# node-circuit-board-v0.net
KiCad netlist of a schematic drawn in EAGLE
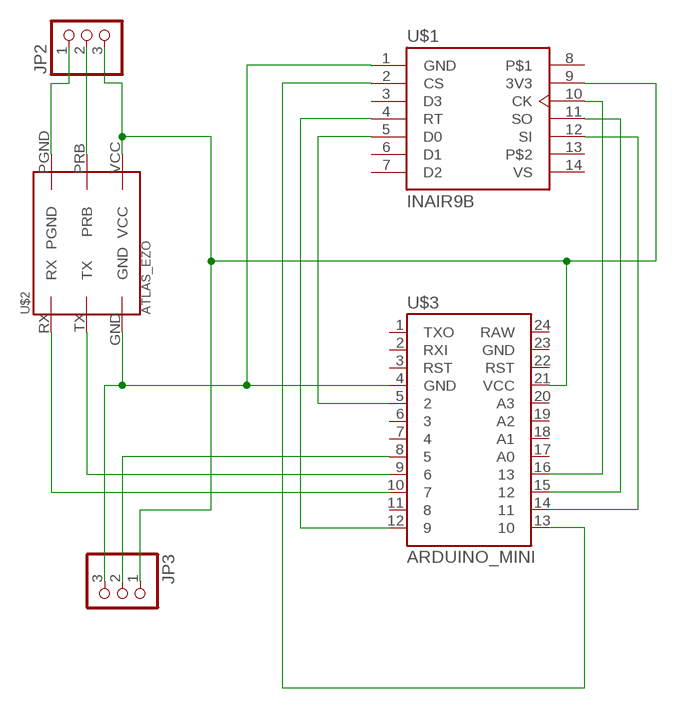
[diagram p0: schematic, sheet 1]

(export (version "E")
  (design (tool "Eeschema 10.0.6"))
  (components
    (comp (ref "JP2")
      (value "PINHD-1X3CB")
      (footprint "eagle-import:1X03-CLEANBIG")
      (libsource (lib "eagle-import") (part "PINHD-1X3CB"))
    )
    (comp (ref "JP3")
      (value "PINHD-1X3CB")
      (footprint "eagle-import:1X03-CLEANBIG")
      (libsource (lib "eagle-import") (part "PINHD-1X3CB"))
    )
    (comp (ref "U$1")
      (value "INAIR9B")
      (footprint "eagle-import:INAIR")
      (libsource (lib "eagle-import") (part "INAIR9B"))
    )
    (comp (ref "U$2")
      (value "ATLAS_EZO")
      (footprint "eagle-import:ATLAS_EZO")
      (libsource (lib "eagle-import") (part "ATLAS_EZO"))
    )
    (comp (ref "U$3")
      (value "ARDUINO_MINI")
      (footprint "eagle-import:ARDUINO_MINI")
      (libsource (lib "eagle-import") (part "ARDUINO_MINI"))
    )
  )
  (nets
    (net (code "1") (name "Net-(JP2-Pad1)") (class "Default")
      (node (ref "JP2") (pin "1") (pinfunction "1_1") (pintype "passive"))
      (node (ref "U$2") (pin "PGND") (pinfunction "PGND_PGND") (pintype "bidirectional"))
    )
    (net (code "2") (name "Net-(JP2-Pad2)") (class "Default")
      (node (ref "JP2") (pin "2") (pinfunction "2_2") (pintype "passive"))
      (node (ref "U$2") (pin "PRB") (pinfunction "PRB_PRB") (pintype "bidirectional"))
    )
    (net (code "3") (name "Net-(U$1-3V3)") (class "Default")
      (node (ref "JP2") (pin "3") (pinfunction "3_3") (pintype "passive"))
      (node (ref "JP3") (pin "1") (pinfunction "1_1") (pintype "passive"))
      (node (ref "U$1") (pin "9") (pinfunction "3V3_9") (pintype "power_in"))
      (node (ref "U$2") (pin "VCC") (pinfunction "VCC_VCC") (pintype "power_in"))
      (node (ref "U$3") (pin "21") (pinfunction "VCC_21") (pintype "bidirectional"))
    )
    (net (code "4") (name "Net-(U$1-CK)") (class "Default")
      (node (ref "U$1") (pin "10") (pinfunction "CK_10") (pintype "input"))
      (node (ref "U$3") (pin "16") (pinfunction "13_16") (pintype "bidirectional"))
    )
    (net (code "5") (name "Net-(U$1-CS)") (class "Default")
      (node (ref "U$1") (pin "2") (pinfunction "CS_2") (pintype "input"))
      (node (ref "U$3") (pin "13") (pinfunction "10_13") (pintype "bidirectional"))
    )
    (net (code "6") (name "Net-(U$1-D0)") (class "Default")
      (node (ref "U$1") (pin "5") (pinfunction "D0_5") (pintype "output"))
      (node (ref "U$3") (pin "5") (pinfunction "2_5") (pintype "bidirectional"))
    )
    (net (code "7") (name "Net-(U$1-GND)") (class "Default")
      (node (ref "JP3") (pin "3") (pinfunction "3_3") (pintype "passive"))
      (node (ref "U$1") (pin "1") (pinfunction "GND_1") (pintype "power_in"))
      (node (ref "U$2") (pin "GND") (pinfunction "GND_GND") (pintype "power_in"))
      (node (ref "U$3") (pin "4") (pinfunction "GND_4") (pintype "bidirectional"))
    )
    (net (code "8") (name "Net-(U$1-RT)") (class "Default")
      (node (ref "U$1") (pin "4") (pinfunction "RT_4") (pintype "input"))
      (node (ref "U$3") (pin "12") (pinfunction "9_12") (pintype "bidirectional"))
    )
    (net (code "9") (name "Net-(U$1-SI)") (class "Default")
      (node (ref "U$1") (pin "12") (pinfunction "SI_12") (pintype "input"))
      (node (ref "U$3") (pin "14") (pinfunction "11_14") (pintype "bidirectional"))
    )
    (net (code "10") (name "Net-(U$1-SO)") (class "Default")
      (node (ref "U$1") (pin "11") (pinfunction "SO_11") (pintype "output"))
      (node (ref "U$3") (pin "15") (pinfunction "12_15") (pintype "bidirectional"))
    )
    (net (code "11") (name "Net-(U$3-5)") (class "Default")
      (node (ref "JP3") (pin "2") (pinfunction "2_2") (pintype "passive"))
      (node (ref "U$3") (pin "8") (pinfunction "5_8") (pintype "bidirectional"))
    )
    (net (code "12") (name "Net-(U$3-6)") (class "Default")
      (node (ref "U$2") (pin "TX") (pinfunction "TX_TX") (pintype "bidirectional"))
      (node (ref "U$3") (pin "9") (pinfunction "6_9") (pintype "bidirectional"))
    )
    (net (code "13") (name "Net-(U$3-7)") (class "Default")
      (node (ref "U$2") (pin "RX") (pinfunction "RX_RX") (pintype "bidirectional"))
      (node (ref "U$3") (pin "10") (pinfunction "7_10") (pintype "bidirectional"))
    )
    (net (code "14") (name "unconnected-(U$1-D1-Pad6)") (class "Default")
      (node (ref "U$1") (pin "6") (pinfunction "D1_6") (pintype "output"))
    )
    (net (code "15") (name "unconnected-(U$1-D2-Pad7)") (class "Default")
      (node (ref "U$1") (pin "7") (pinfunction "D2_7") (pintype "output"))
    )
    (net (code "16") (name "unconnected-(U$1-D3-Pad3)") (class "Default")
      (node (ref "U$1") (pin "3") (pinfunction "D3_3") (pintype "output"))
    )
    (net (code "17") (name "unconnected-(U$1-P$1-Pad8)") (class "Default")
      (node (ref "U$1") (pin "8") (pinfunction "P$1_8") (pintype "bidirectional"))
    )
    (net (code "18") (name "unconnected-(U$1-P$2-Pad13)") (class "Default")
      (node (ref "U$1") (pin "13") (pinfunction "P$2_13") (pintype "bidirectional"))
    )
    (net (code "19") (name "unconnected-(U$1-VS-Pad14)") (class "Default")
      (node (ref "U$1") (pin "14") (pinfunction "VS_14") (pintype "bidirectional"))
    )
    (net (code "20") (name "unconnected-(U$3-3-Pad6)") (class "Default")
      (node (ref "U$3") (pin "6") (pinfunction "3_6") (pintype "bidirectional"))
    )
    (net (code "21") (name "unconnected-(U$3-4-Pad7)") (class "Default")
      (node (ref "U$3") (pin "7") (pinfunction "4_7") (pintype "bidirectional"))
    )
    (net (code "22") (name "unconnected-(U$3-8-Pad11)") (class "Default")
      (node (ref "U$3") (pin "11") (pinfunction "8_11") (pintype "bidirectional"))
    )
    (net (code "23") (name "unconnected-(U$3-A0-Pad17)") (class "Default")
      (node (ref "U$3") (pin "17") (pinfunction "A0_17") (pintype "bidirectional"))
    )
    (net (code "24") (name "unconnected-(U$3-A1-Pad18)") (class "Default")
      (node (ref "U$3") (pin "18") (pinfunction "A1_18") (pintype "bidirectional"))
    )
    (net (code "25") (name "unconnected-(U$3-A2-Pad19)") (class "Default")
      (node (ref "U$3") (pin "19") (pinfunction "A2_19") (pintype "bidirectional"))
    )
    (net (code "26") (name "unconnected-(U$3-A3-Pad20)") (class "Default")
      (node (ref "U$3") (pin "20") (pinfunction "A3_20") (pintype "bidirectional"))
    )
    (net (code "27") (name "unconnected-(U$3-GND-Pad23)") (class "Default")
      (node (ref "U$3") (pin "23") (pinfunction "GND_23") (pintype "bidirectional"))
    )
    (net (code "28") (name "unconnected-(U$3-RAW-Pad24)") (class "Default")
      (node (ref "U$3") (pin "24") (pinfunction "RAW_24") (pintype "bidirectional"))
    )
    (net (code "29") (name "unconnected-(U$3-RST-Pad3)") (class "Default")
      (node (ref "U$3") (pin "3") (pinfunction "RST_3") (pintype "bidirectional"))
    )
    (net (code "30") (name "unconnected-(U$3-RST-Pad22)") (class "Default")
      (node (ref "U$3") (pin "22") (pinfunction "RST_22") (pintype "bidirectional"))
    )
    (net (code "31") (name "unconnected-(U$3-RXI-Pad2)") (class "Default")
      (node (ref "U$3") (pin "2") (pinfunction "RXI_2") (pintype "bidirectional"))
    )
    (net (code "32") (name "unconnected-(U$3-TXO-Pad1)") (class "Default")
      (node (ref "U$3") (pin "1") (pinfunction "TXO_1") (pintype "bidirectional"))
    )
  )
)
